# SAM-M10Q.net
KiCad netlist of a schematic drawn in Altium Designer
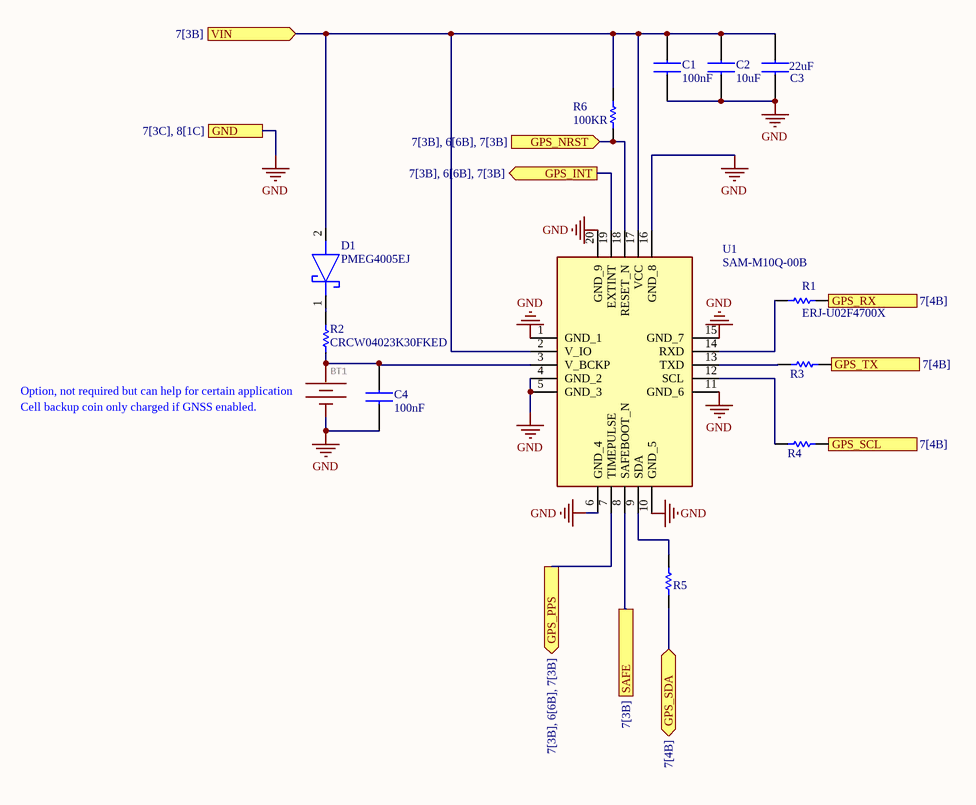
[diagram p0: SAM-M10Q.SchDoc]

(export (version "E")
  (design (tool "Eeschema 10.0.6"))
  (components
    (comp (ref "BT1")
      (value "6.8MM_COIN_CELL")
      (footprint "MS421R_IV03E")
      (description "SEIKO Reflowable Lithium Batteries")
      (libsource (lib "stm32wl-dev") (part "RELOWABLE_BATTERY_MS421R"))
    )
    (comp (ref "C1")
      (value "100nF")
      (footprint "CAPC0603X33N")
      (description "Multilayer Ceramic Capacitors MLCC - SMD/SMT .1UF     16V   10%        0201")
      (fields
        (field (name "MOUSER PART NUMBER") "81-GRM033Z71C104KE4D")
        (field (name "MANUFACTURER_PART_NUMBER") "GRM033Z71C104KE14D")
      )
      (libsource (lib "stm32wl-dev") (part "GRM033Z71C104KE14D"))
    )
    (comp (ref "C2")
      (value "10uF")
      (footprint "CAPC1608X90N")
      (description "Multilayer Ceramic Capacitors MLCC - SMD/SMT 10 uF 10 VDC 20% 0603 X5R")
      (fields
        (field (name "MANUFACTURER_PART_NUMBER") "GRM188R61A106MAALJ")
        (field (name "MOUSER PART NUMBER") "81-GRM188R61A106MALJ")
      )
      (libsource (lib "stm32wl-dev") (part "GRM188R61A106MAALJ"))
    )
    (comp (ref "C3")
      (value "22uF")
      (footprint "GRM18x")
      (description "Multilayer Ceramic Capacitors MLCC - SMD/SMT 22 uF 10 VDC 20% 0603 X5R")
      (fields
        (field (name "MANUFACTURER_PART_NUMBER") "GRM188R61A226ME15D")
        (field (name "MOUSER PART NUMBER") "81-GRM188R61A226ME5D")
      )
      (libsource (lib "stm32wl-dev") (part "GRM188R61A226ME15D"))
    )
    (comp (ref "C4")
      (value "100nF")
      (footprint "CAPC0603X33N")
      (description "Multilayer Ceramic Capacitors MLCC - SMD/SMT .1UF     16V   10%        0201")
      (fields
        (field (name "MOUSER PART NUMBER") "81-GRM033Z71C104KE4D")
        (field (name "MANUFACTURER_PART_NUMBER") "GRM033Z71C104KE14D")
      )
      (libsource (lib "stm32wl-dev") (part "GRM033Z71C104KE14D"))
    )
    (comp (ref "D1")
      (value "PMEG4005EJ")
      (footprint "SOD2512X80N")
      (description "Schottky Diodes & Rectifiers")
      (libsource (lib "stm32wl-dev") (part "PMEG4005EJ"))
    )
    (comp (ref "R1")
      (value "ERJ-U02F4700X")
      (footprint "ERJS02_U02_(0402)")
      (description "Thick Film Resistors - SMD 1/20watt 470ohms 1% 200ppm")
      (fields (field (name "MOUSER PART NUMBER") "667-ERJ-U02F4700X"))
      (libsource (lib "stm32wl-dev") (part "ERJ-U02F4700X"))
    )
    (comp (ref "R2")
      (value "CRCW04023K30FKED")
      (footprint "RESC1005X40N")
      (description "Thick Film Resistors - SMD 1/16watt 3.3Kohms 1% 100ppm")
      (fields (field (name "MOUSER PART NUMBER") "71-CRCW0402-3.3K-E3"))
      (libsource (lib "stm32wl-dev") (part "CRCW04023K30FKED"))
    )
    (comp (ref "R3")
      (value "ERJ-U02F4700X")
      (footprint "ERJS02_U02_(0402)")
      (description "Thick Film Resistors - SMD 1/20watt 470ohms 1% 200ppm")
      (fields (field (name "MOUSER PART NUMBER") "667-ERJ-U02F4700X"))
      (libsource (lib "stm32wl-dev") (part "ERJ-U02F4700X"))
    )
    (comp (ref "R4")
      (value "ERJ-U02F22R0X")
      (footprint "ERJS02_U02_(0402)")
      (description "Thick Film Resistors - SMD 1/20watt 22ohms 1% 200ppm")
      (libsource (lib "stm32wl-dev") (part "ERJ-U02F22R0X"))
    )
    (comp (ref "R5")
      (value "ERJ-U02F22R0X")
      (footprint "ERJS02_U02_(0402)")
      (description "Thick Film Resistors - SMD 1/20watt 22ohms 1% 200ppm")
      (libsource (lib "stm32wl-dev") (part "ERJ-U02F22R0X"))
    )
    (comp (ref "R6")
      (value "100KR")
      (footprint "ERJPA2_(0402)")
      (description "Thick Film Resistors - SMD HP02 (0402) 1/5W 1% 100kR T/R-10000")
      (fields
        (field (name "MANUFACTURER_PART_NUMBER") "ERJ-PA2F1003X")
        (field (name "MOUSER PART NUMBER") "667-ERJ-PA2F1003X")
      )
      (libsource (lib "stm32wl-dev") (part "ERJ-PA2F1003X"))
    )
    (comp (ref "U1")
      (value "SAM-M10Q-00B")
      (footprint "SAMM10Q00B")
      (description "GNSS / GPS Modules u-blox M10 GNSS antenna module ROM, TCXO, SAW, LNA LGA, 16x16 mm")
      (fields (field (name "MOUSER PART NUMBER") "377-SAM-M10Q-00B"))
      (libsource (lib "stm32wl-dev") (part "SAM-M10Q-00B"))
    )
  )
  (nets
    (net (code "1") (name "/GPS_INT") (class "Default")
      (node (ref "U1") (pin "19") (pinfunction "EXTINT_19") (pintype "passive"))
    )
    (net (code "2") (name "/GPS_NRST") (class "Default")
      (node (ref "R6") (pin "2") (pinfunction "2_2") (pintype "passive"))
      (node (ref "U1") (pin "18") (pinfunction "RESET_N_18") (pintype "passive"))
    )
    (net (code "3") (name "/GPS_PPS") (class "Default")
      (node (ref "U1") (pin "7") (pinfunction "TIMEPULSE_7") (pintype "passive"))
    )
    (net (code "4") (name "/GPS_RX") (class "Default")
      (node (ref "R1") (pin "2") (pinfunction "2_2") (pintype "passive"))
    )
    (net (code "5") (name "/GPS_SCL") (class "Default")
      (node (ref "R4") (pin "2") (pinfunction "2_2") (pintype "passive"))
    )
    (net (code "6") (name "/GPS_SDA") (class "Default")
      (node (ref "R5") (pin "1") (pinfunction "1_1") (pintype "passive"))
    )
    (net (code "7") (name "/GPS_TX") (class "Default")
      (node (ref "R3") (pin "2") (pinfunction "2_2") (pintype "passive"))
    )
    (net (code "8") (name "/SAFE") (class "Default")
      (node (ref "U1") (pin "8") (pinfunction "SAFEBOOT_N_8") (pintype "passive"))
    )
    (net (code "9") (name "/VIN") (class "Default")
      (node (ref "C1") (pin "1") (pinfunction "1_1") (pintype "passive"))
      (node (ref "C2") (pin "2") (pinfunction "2_2") (pintype "passive"))
      (node (ref "C3") (pin "2") (pinfunction "2_2") (pintype "passive"))
      (node (ref "D1") (pin "2") (pinfunction "A_2") (pintype "passive"))
      (node (ref "R6") (pin "1") (pinfunction "1_1") (pintype "passive"))
      (node (ref "U1") (pin "17") (pinfunction "VCC_17") (pintype "passive"))
      (node (ref "U1") (pin "2") (pinfunction "V_IO_2") (pintype "passive"))
    )
    (net (code "10") (name "GND") (class "Default")
      (node (ref "BT1") (pin "-") (pinfunction "-_-") (pintype "power_in"))
      (node (ref "C1") (pin "2") (pinfunction "2_2") (pintype "passive"))
      (node (ref "C2") (pin "1") (pinfunction "1_1") (pintype "passive"))
      (node (ref "C3") (pin "1") (pinfunction "1_1") (pintype "passive"))
      (node (ref "C4") (pin "1") (pinfunction "1_1") (pintype "passive"))
      (node (ref "U1") (pin "1") (pinfunction "GND_1_1") (pintype "passive"))
      (node (ref "U1") (pin "10") (pinfunction "GND_5_10") (pintype "passive"))
      (node (ref "U1") (pin "11") (pinfunction "GND_6_11") (pintype "passive"))
      (node (ref "U1") (pin "15") (pinfunction "GND_7_15") (pintype "passive"))
      (node (ref "U1") (pin "16") (pinfunction "GND_8_16") (pintype "passive"))
      (node (ref "U1") (pin "20") (pinfunction "GND_9_20") (pintype "passive"))
      (node (ref "U1") (pin "4") (pinfunction "GND_2_4") (pintype "passive"))
      (node (ref "U1") (pin "5") (pinfunction "GND_3_5") (pintype "passive"))
      (node (ref "U1") (pin "6") (pinfunction "GND_4_6") (pintype "passive"))
    )
    (net (code "11") (name "Net-(D1-K)") (class "Default")
      (node (ref "D1") (pin "1") (pinfunction "K_1") (pintype "passive"))
      (node (ref "R2") (pin "2") (pinfunction "2_2") (pintype "passive"))
    )
    (net (code "12") (name "Net-(U1-RXD)") (class "Default")
      (node (ref "R1") (pin "1") (pinfunction "1_1") (pintype "passive"))
      (node (ref "U1") (pin "14") (pinfunction "RXD_14") (pintype "passive"))
    )
    (net (code "13") (name "Net-(U1-SCL)") (class "Default")
      (node (ref "R4") (pin "1") (pinfunction "1_1") (pintype "passive"))
      (node (ref "U1") (pin "12") (pinfunction "SCL_12") (pintype "passive"))
    )
    (net (code "14") (name "Net-(U1-SDA)") (class "Default")
      (node (ref "R5") (pin "2") (pinfunction "2_2") (pintype "passive"))
      (node (ref "U1") (pin "9") (pinfunction "SDA_9") (pintype "passive"))
    )
    (net (code "15") (name "Net-(U1-TXD)") (class "Default")
      (node (ref "R3") (pin "1") (pinfunction "1_1") (pintype "passive"))
      (node (ref "U1") (pin "13") (pinfunction "TXD_13") (pintype "passive"))
    )
    (net (code "16") (name "Net-(U1-V_BCKP)") (class "Default")
      (node (ref "BT1") (pin "+") (pinfunction "+_+") (pintype "power_in"))
      (node (ref "C4") (pin "2") (pinfunction "2_2") (pintype "passive"))
      (node (ref "R2") (pin "1") (pinfunction "1_1") (pintype "passive"))
      (node (ref "U1") (pin "3") (pinfunction "V_BCKP_3") (pintype "passive"))
    )
  )
)
